# 10_-MODEM_CONNECTORS.net
KiCad netlist of a schematic drawn in Altium Designer
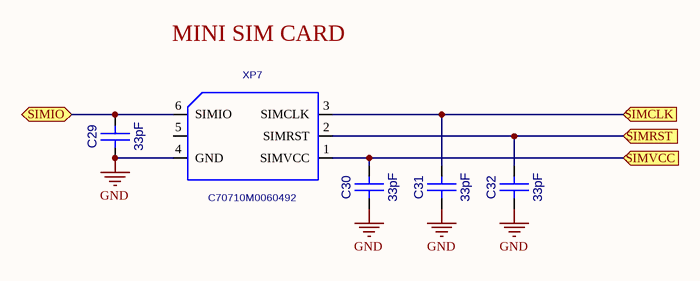
[diagram p0: [10]-MODEM_CONNECTORS.SchDoc]

(export (version "E")
  (design (tool "Eeschema 10.0.6"))
  (components
    (comp (ref "C29")
      (value "33pF")
      (footprint "CC0603")
      (description "CC0603")
      (libsource (lib "gprs_modem_2") (part "CC0603"))
    )
    (comp (ref "C30")
      (value "33pF")
      (footprint "CC0603")
      (description "CC0603")
      (libsource (lib "gprs_modem_2") (part "CC0603"))
    )
    (comp (ref "C31")
      (value "33pF")
      (footprint "CC0603")
      (description "CC0603")
      (libsource (lib "gprs_modem_2") (part "CC0603"))
    )
    (comp (ref "C32")
      (value "33pF")
      (footprint "CC0603")
      (description "CC0603")
      (libsource (lib "gprs_modem_2") (part "CC0603"))
    )
    (comp (ref "XP7")
      (value "C70710M0060492")
      (footprint "SCVW06A25020")
      (description "SCV-W06A25-020")
      (libsource (lib "gprs_modem_2") (part "SCV-W06A25-020"))
    )
  )
  (nets
    (net (code "1") (name "/SIMCLK") (class "Default")
      (node (ref "C31") (pin "2") (pinfunction "B_2") (pintype "passive"))
      (node (ref "XP7") (pin "3") (pinfunction "SIMCLK_3") (pintype "passive"))
    )
    (net (code "2") (name "/SIMIO") (class "Default")
      (node (ref "C29") (pin "2") (pinfunction "B_2") (pintype "passive"))
      (node (ref "XP7") (pin "6") (pinfunction "SIMIO_6") (pintype "passive"))
    )
    (net (code "3") (name "/SIMRST") (class "Default")
      (node (ref "C32") (pin "2") (pinfunction "B_2") (pintype "passive"))
      (node (ref "XP7") (pin "2") (pinfunction "SIMRST_2") (pintype "passive"))
    )
    (net (code "4") (name "/SIMVCC") (class "Default")
      (node (ref "C30") (pin "2") (pinfunction "B_2") (pintype "passive"))
      (node (ref "XP7") (pin "1") (pinfunction "SIMVCC_1") (pintype "passive"))
    )
    (net (code "5") (name "GND") (class "Default")
      (node (ref "C29") (pin "1") (pinfunction "A_1") (pintype "passive"))
      (node (ref "C30") (pin "1") (pinfunction "A_1") (pintype "passive"))
      (node (ref "C31") (pin "1") (pinfunction "A_1") (pintype "passive"))
      (node (ref "C32") (pin "1") (pinfunction "A_1") (pintype "passive"))
      (node (ref "XP7") (pin "4") (pinfunction "GND_4") (pintype "passive"))
    )
    (net (code "6") (name "unconnected-(XP7-Pad5)") (class "Default")
      (node (ref "XP7") (pin "5") (pintype "passive"))
    )
  )
)
